# SERIAL_FMU_REV_1B.net
KiCad netlist of a schematic drawn in Altium Designer
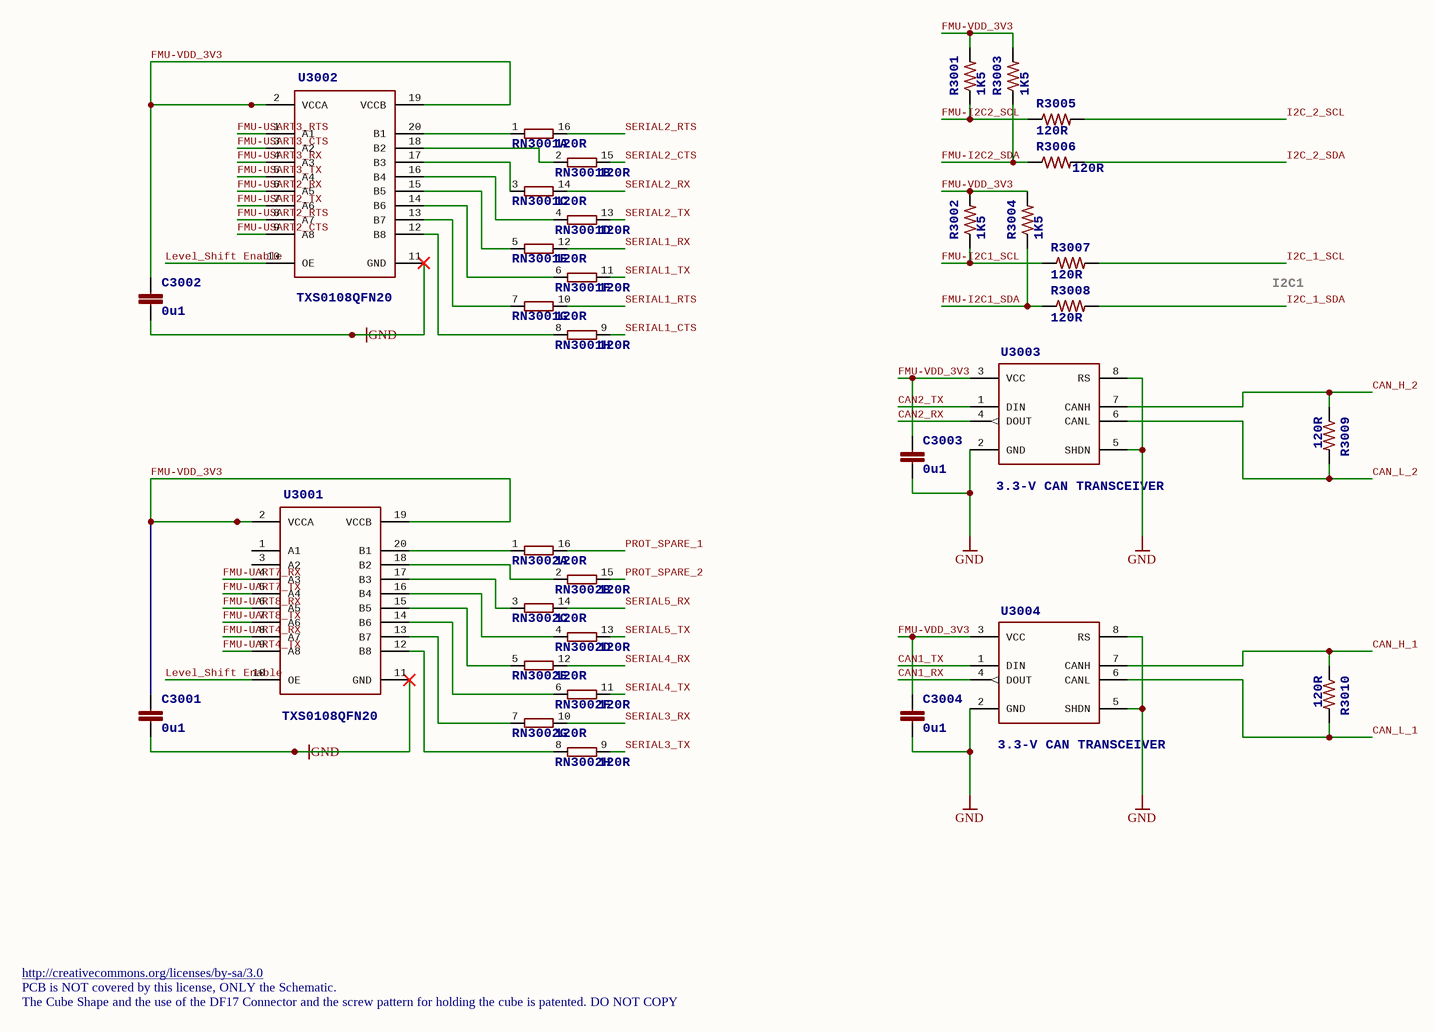
[diagram p0: SERIAL_FMU_REV_1B.SchDoc]

(export (version "E")
  (design (tool "Eeschema 10.0.6"))
  (components
    (comp (ref "C3001")
      (value "0u1")
      (footprint "0402-CAP")
      (description "CAP CER 0.1UF 16V Y5V 0402")
      (libsource (lib "pixhawk2") (part "CAP0402"))
    )
    (comp (ref "C3002")
      (value "0u1")
      (footprint "0402-CAP")
      (description "CAP CER 0.1UF 16V Y5V 0402")
      (libsource (lib "pixhawk2") (part "CAP0402"))
    )
    (comp (ref "C3003")
      (value "0u1")
      (footprint "0402-CAP")
      (description "CAP CER 0.1UF 16V Y5V 0402")
      (libsource (lib "pixhawk2") (part "CAP0402"))
    )
    (comp (ref "C3004")
      (value "0u1")
      (footprint "0402-CAP")
      (description "CAP CER 0.1UF 16V Y5V 0402")
      (libsource (lib "pixhawk2") (part "CAP0402"))
    )
    (comp (ref "R3001")
      (value "1K5")
      (footprint "0402-RES")
      (description "RES 1.5K OHM 1/16W 1% 0402 SMD")
      (libsource (lib "pixhawk2") (part "RESISTOR0402-RES"))
    )
    (comp (ref "R3002")
      (value "1K5")
      (footprint "0402-RES")
      (description "RES 1.5K OHM 1/16W 1% 0402 SMD")
      (libsource (lib "pixhawk2") (part "RESISTOR0402-RES"))
    )
    (comp (ref "R3003")
      (value "1K5")
      (footprint "0402-RES")
      (description "RES 1.5K OHM 1/16W 1% 0402 SMD")
      (libsource (lib "pixhawk2") (part "RESISTOR0402-RES"))
    )
    (comp (ref "R3004")
      (value "1K5")
      (footprint "0402-RES")
      (description "RES 1.5K OHM 1/16W 1% 0402 SMD")
      (libsource (lib "pixhawk2") (part "RESISTOR0402-RES"))
    )
    (comp (ref "R3005")
      (value "120R")
      (footprint "0402-RES")
      (description "RES 120 OHM 1/16W 1% 0402 SMD")
      (libsource (lib "pixhawk2") (part "RESISTOR0402-RES"))
    )
    (comp (ref "R3006")
      (value "120R")
      (footprint "0402-RES")
      (description "RES 120 OHM 1/16W 1% 0402 SMD")
      (libsource (lib "pixhawk2") (part "RESISTOR0402-RES"))
    )
    (comp (ref "R3007")
      (value "120R")
      (footprint "0402-RES")
      (description "RES 120 OHM 1/16W 1% 0402 SMD")
      (libsource (lib "pixhawk2") (part "RESISTOR0402-RES"))
    )
    (comp (ref "R3008")
      (value "120R")
      (footprint "0402-RES")
      (description "RES 120 OHM 1/16W 1% 0402 SMD")
      (libsource (lib "pixhawk2") (part "RESISTOR0402-RES"))
    )
    (comp (ref "R3009")
      (value "120R")
      (footprint "0402-RES")
      (description "RES 120 OHM 1/16W 1% 0402 SMD")
      (libsource (lib "pixhawk2") (part "RESISTOR0402-RES"))
    )
    (comp (ref "R3010")
      (value "120R")
      (footprint "0402-RES")
      (description "RES 120 OHM 1/16W 1% 0402 SMD")
      (libsource (lib "pixhawk2") (part "RESISTOR0402-RES"))
    )
    (comp (ref "RN3001")
      (value "120R")
      (footprint "EXB2HV")
      (description "RES ARRAY 120 OHM 8 RES 1506")
      (libsource (lib "pixhawk2") (part "8R-NEXB2HV-120R"))
    )
    (comp (ref "RN3002")
      (value "120R")
      (footprint "EXB2HV")
      (description "RES ARRAY 120 OHM 8 RES 1506")
      (libsource (lib "pixhawk2") (part "8R-NEXB2HV-120R"))
    )
    (comp (ref "U3001")
      (value "TXS0108QFN20")
      (footprint "QFN20-RGY")
      (description "IC XLATR VOLT-LVL 8B BDIR 20QFN")
      (libsource (lib "pixhawk2") (part "TXS0108QFN20"))
    )
    (comp (ref "U3002")
      (value "TXS0108QFN20")
      (footprint "QFN20-RGY")
      (description "IC XLATR VOLT-LVL 8B BDIR 20QFN")
      (libsource (lib "pixhawk2") (part "TXS0108QFN20"))
    )
    (comp (ref "U3003")
      (value "3.3-V CAN TRANSCEIVER")
      (footprint "SOT23-8")
      (description "IC TXRX CAN 1MBPS SOT23-8")
      (libsource (lib "pixhawk2") (part "MAX3051MAX3051EKA"))
    )
    (comp (ref "U3004")
      (value "3.3-V CAN TRANSCEIVER")
      (footprint "SOT23-8")
      (description "IC TXRX CAN 1MBPS SOT23-8")
      (libsource (lib "pixhawk2") (part "MAX3051MAX3051EKA"))
    )
  )
  (nets
    (net (code "1") (name "/CAN1_RX") (class "Default")
      (node (ref "U3004") (pin "4") (pinfunction "DOUT_4") (pintype "output"))
    )
    (net (code "2") (name "/CAN1_TX") (class "Default")
      (node (ref "U3004") (pin "1") (pinfunction "DIN_1") (pintype "passive"))
    )
    (net (code "3") (name "/CAN2_RX") (class "Default")
      (node (ref "U3003") (pin "4") (pinfunction "DOUT_4") (pintype "output"))
    )
    (net (code "4") (name "/CAN2_TX") (class "Default")
      (node (ref "U3003") (pin "1") (pinfunction "DIN_1") (pintype "passive"))
    )
    (net (code "5") (name "/CAN_H_1") (class "Default")
      (node (ref "R3010") (pin "P$1") (pinfunction "1_P$1") (pintype "passive"))
      (node (ref "U3004") (pin "7") (pinfunction "CANH_7") (pintype "passive"))
    )
    (net (code "6") (name "/CAN_H_2") (class "Default")
      (node (ref "R3009") (pin "P$1") (pinfunction "1_P$1") (pintype "passive"))
      (node (ref "U3003") (pin "7") (pinfunction "CANH_7") (pintype "passive"))
    )
    (net (code "7") (name "/CAN_L_1") (class "Default")
      (node (ref "R3010") (pin "P$2") (pinfunction "2_P$2") (pintype "passive"))
      (node (ref "U3004") (pin "6") (pinfunction "CANL_6") (pintype "passive"))
    )
    (net (code "8") (name "/CAN_L_2") (class "Default")
      (node (ref "R3009") (pin "P$2") (pinfunction "2_P$2") (pintype "passive"))
      (node (ref "U3003") (pin "6") (pinfunction "CANL_6") (pintype "passive"))
    )
    (net (code "9") (name "/FMU-I2C1_SCL") (class "Default")
      (node (ref "R3002") (pin "P$1") (pinfunction "1_P$1") (pintype "passive"))
      (node (ref "R3007") (pin "P$1") (pinfunction "1_P$1") (pintype "passive"))
    )
    (net (code "10") (name "/FMU-I2C1_SDA") (class "Default")
      (node (ref "R3004") (pin "P$1") (pinfunction "1_P$1") (pintype "passive"))
      (node (ref "R3008") (pin "P$1") (pinfunction "1_P$1") (pintype "passive"))
    )
    (net (code "11") (name "/FMU-I2C2_SCL") (class "Default")
      (node (ref "R3001") (pin "P$1") (pinfunction "1_P$1") (pintype "passive"))
      (node (ref "R3005") (pin "P$1") (pinfunction "1_P$1") (pintype "passive"))
    )
    (net (code "12") (name "/FMU-I2C2_SDA") (class "Default")
      (node (ref "R3003") (pin "P$1") (pinfunction "1_P$1") (pintype "passive"))
      (node (ref "R3006") (pin "P$1") (pinfunction "1_P$1") (pintype "passive"))
    )
    (net (code "13") (name "/FMU-UART4_RX") (class "Default")
      (node (ref "U3001") (pin "8") (pinfunction "A7_8") (pintype "passive"))
    )
    (net (code "14") (name "/FMU-UART4_TX") (class "Default")
      (node (ref "U3001") (pin "9") (pinfunction "A8_9") (pintype "passive"))
    )
    (net (code "15") (name "/FMU-UART7_RX") (class "Default")
      (node (ref "U3001") (pin "4") (pinfunction "A3_4") (pintype "passive"))
    )
    (net (code "16") (name "/FMU-UART7_TX") (class "Default")
      (node (ref "U3001") (pin "5") (pinfunction "A4_5") (pintype "passive"))
    )
    (net (code "17") (name "/FMU-UART8_RX") (class "Default")
      (node (ref "U3001") (pin "6") (pinfunction "A5_6") (pintype "passive"))
    )
    (net (code "18") (name "/FMU-UART8_TX") (class "Default")
      (node (ref "U3001") (pin "7") (pinfunction "A6_7") (pintype "passive"))
    )
    (net (code "19") (name "/FMU-USART2_CTS") (class "Default")
      (node (ref "U3002") (pin "9") (pinfunction "A8_9") (pintype "passive"))
    )
    (net (code "20") (name "/FMU-USART2_RTS") (class "Default")
      (node (ref "U3002") (pin "8") (pinfunction "A7_8") (pintype "passive"))
    )
    (net (code "21") (name "/FMU-USART2_RX") (class "Default")
      (node (ref "U3002") (pin "6") (pinfunction "A5_6") (pintype "passive"))
    )
    (net (code "22") (name "/FMU-USART2_TX") (class "Default")
      (node (ref "U3002") (pin "7") (pinfunction "A6_7") (pintype "passive"))
    )
    (net (code "23") (name "/FMU-USART3_CTS") (class "Default")
      (node (ref "U3002") (pin "3") (pinfunction "A2_3") (pintype "passive"))
    )
    (net (code "24") (name "/FMU-USART3_RTS") (class "Default")
      (node (ref "U3002") (pin "1") (pinfunction "A1_1") (pintype "passive"))
    )
    (net (code "25") (name "/FMU-USART3_RX") (class "Default")
      (node (ref "U3002") (pin "4") (pinfunction "A3_4") (pintype "passive"))
    )
    (net (code "26") (name "/FMU-USART3_TX") (class "Default")
      (node (ref "U3002") (pin "5") (pinfunction "A4_5") (pintype "passive"))
    )
    (net (code "27") (name "/FMU-VDD_3V3") (class "Default")
      (node (ref "C3001") (pin "P$1") (pinfunction "1_P$1") (pintype "passive"))
      (node (ref "C3002") (pin "P$1") (pinfunction "1_P$1") (pintype "passive"))
      (node (ref "C3003") (pin "P$1") (pinfunction "1_P$1") (pintype "passive"))
      (node (ref "C3004") (pin "P$1") (pinfunction "1_P$1") (pintype "passive"))
      (node (ref "R3001") (pin "P$2") (pinfunction "2_P$2") (pintype "passive"))
      (node (ref "R3002") (pin "P$2") (pinfunction "2_P$2") (pintype "passive"))
      (node (ref "R3003") (pin "P$2") (pinfunction "2_P$2") (pintype "passive"))
      (node (ref "R3004") (pin "P$2") (pinfunction "2_P$2") (pintype "passive"))
      (node (ref "U3001") (pin "19") (pinfunction "VCCB_19") (pintype "passive"))
      (node (ref "U3001") (pin "2") (pinfunction "VCCA_2") (pintype "passive"))
      (node (ref "U3002") (pin "19") (pinfunction "VCCB_19") (pintype "passive"))
      (node (ref "U3002") (pin "2") (pinfunction "VCCA_2") (pintype "passive"))
      (node (ref "U3003") (pin "3") (pinfunction "VCC_3") (pintype "passive"))
      (node (ref "U3004") (pin "3") (pinfunction "VCC_3") (pintype "passive"))
    )
    (net (code "28") (name "/I2C_1_SCL") (class "Default")
      (node (ref "R3007") (pin "P$2") (pinfunction "2_P$2") (pintype "passive"))
    )
    (net (code "29") (name "/I2C_1_SDA") (class "Default")
      (node (ref "R3008") (pin "P$2") (pinfunction "2_P$2") (pintype "passive"))
    )
    (net (code "30") (name "/I2C_2_SCL") (class "Default")
      (node (ref "R3005") (pin "P$2") (pinfunction "2_P$2") (pintype "passive"))
    )
    (net (code "31") (name "/I2C_2_SDA") (class "Default")
      (node (ref "R3006") (pin "P$2") (pinfunction "2_P$2") (pintype "passive"))
    )
    (net (code "32") (name "/Level_Shift Enable") (class "Default")
      (node (ref "U3001") (pin "10") (pinfunction "OE_10") (pintype "passive"))
      (node (ref "U3002") (pin "10") (pinfunction "OE_10") (pintype "passive"))
    )
    (net (code "33") (name "/PROT_SPARE_1") (class "Default")
      (node (ref "RN3002") (pin "16") (pinfunction "2_16") (pintype "passive"))
    )
    (net (code "34") (name "/PROT_SPARE_2") (class "Default")
      (node (ref "RN3002") (pin "15") (pinfunction "2_15") (pintype "passive"))
    )
    (net (code "35") (name "/SERIAL1_CTS") (class "Default")
      (node (ref "RN3001") (pin "9") (pinfunction "2_9") (pintype "passive"))
    )
    (net (code "36") (name "/SERIAL1_RTS") (class "Default")
      (node (ref "RN3001") (pin "10") (pinfunction "2_10") (pintype "passive"))
    )
    (net (code "37") (name "/SERIAL1_RX") (class "Default")
      (node (ref "RN3001") (pin "12") (pinfunction "2_12") (pintype "passive"))
    )
    (net (code "38") (name "/SERIAL1_TX") (class "Default")
      (node (ref "RN3001") (pin "11") (pinfunction "2_11") (pintype "passive"))
    )
    (net (code "39") (name "/SERIAL2_CTS") (class "Default")
      (node (ref "RN3001") (pin "15") (pinfunction "2_15") (pintype "passive"))
    )
    (net (code "40") (name "/SERIAL2_RTS") (class "Default")
      (node (ref "RN3001") (pin "16") (pinfunction "2_16") (pintype "passive"))
    )
    (net (code "41") (name "/SERIAL2_RX") (class "Default")
      (node (ref "RN3001") (pin "14") (pinfunction "2_14") (pintype "passive"))
    )
    (net (code "42") (name "/SERIAL2_TX") (class "Default")
      (node (ref "RN3001") (pin "13") (pinfunction "2_13") (pintype "passive"))
    )
    (net (code "43") (name "/SERIAL3_RX") (class "Default")
      (node (ref "RN3002") (pin "10") (pinfunction "2_10") (pintype "passive"))
    )
    (net (code "44") (name "/SERIAL3_TX") (class "Default")
      (node (ref "RN3002") (pin "9") (pinfunction "2_9") (pintype "passive"))
    )
    (net (code "45") (name "/SERIAL4_RX") (class "Default")
      (node (ref "RN3002") (pin "12") (pinfunction "2_12") (pintype "passive"))
    )
    (net (code "46") (name "/SERIAL4_TX") (class "Default")
      (node (ref "RN3002") (pin "11") (pinfunction "2_11") (pintype "passive"))
    )
    (net (code "47") (name "/SERIAL5_RX") (class "Default")
      (node (ref "RN3002") (pin "14") (pinfunction "2_14") (pintype "passive"))
    )
    (net (code "48") (name "/SERIAL5_TX") (class "Default")
      (node (ref "RN3002") (pin "13") (pinfunction "2_13") (pintype "passive"))
    )
    (net (code "49") (name "GND") (class "Default")
      (node (ref "C3001") (pin "P$2") (pinfunction "2_P$2") (pintype "passive"))
      (node (ref "C3002") (pin "P$2") (pinfunction "2_P$2") (pintype "passive"))
      (node (ref "C3003") (pin "P$2") (pinfunction "2_P$2") (pintype "passive"))
      (node (ref "C3004") (pin "P$2") (pinfunction "2_P$2") (pintype "passive"))
      (node (ref "U3001") (pin "11") (pinfunction "GND_11") (pintype "open_emitter"))
      (node (ref "U3002") (pin "11") (pinfunction "GND_11") (pintype "open_emitter"))
      (node (ref "U3003") (pin "2") (pinfunction "GND_2") (pintype "open_emitter"))
      (node (ref "U3003") (pin "5") (pinfunction "SHDN_5") (pintype "passive"))
      (node (ref "U3003") (pin "8") (pinfunction "RS_8") (pintype "passive"))
      (node (ref "U3004") (pin "2") (pinfunction "GND_2") (pintype "open_emitter"))
      (node (ref "U3004") (pin "5") (pinfunction "SHDN_5") (pintype "passive"))
      (node (ref "U3004") (pin "8") (pinfunction "RS_8") (pintype "passive"))
    )
    (net (code "50") (name "Net-(RN3001B-1)") (class "Default")
      (node (ref "RN3001") (pin "2") (pinfunction "1_2") (pintype "passive"))
      (node (ref "U3002") (pin "18") (pinfunction "B2_18") (pintype "passive"))
    )
    (net (code "51") (name "Net-(RN3001C-1)") (class "Default")
      (node (ref "RN3001") (pin "3") (pinfunction "1_3") (pintype "passive"))
      (node (ref "U3002") (pin "17") (pinfunction "B3_17") (pintype "passive"))
    )
    (net (code "52") (name "Net-(RN3001D-1)") (class "Default")
      (node (ref "RN3001") (pin "4") (pinfunction "1_4") (pintype "passive"))
      (node (ref "U3002") (pin "16") (pinfunction "B4_16") (pintype "passive"))
    )
    (net (code "53") (name "Net-(RN3001E-1)") (class "Default")
      (node (ref "RN3001") (pin "5") (pinfunction "1_5") (pintype "passive"))
      (node (ref "U3002") (pin "15") (pinfunction "B5_15") (pintype "passive"))
    )
    (net (code "54") (name "Net-(RN3001F-1)") (class "Default")
      (node (ref "RN3001") (pin "6") (pinfunction "1_6") (pintype "passive"))
      (node (ref "U3002") (pin "14") (pinfunction "B6_14") (pintype "passive"))
    )
    (net (code "55") (name "Net-(RN3001G-1)") (class "Default")
      (node (ref "RN3001") (pin "7") (pinfunction "1_7") (pintype "passive"))
      (node (ref "U3002") (pin "13") (pinfunction "B7_13") (pintype "passive"))
    )
    (net (code "56") (name "Net-(RN3001H-1)") (class "Default")
      (node (ref "RN3001") (pin "8") (pinfunction "1_8") (pintype "passive"))
      (node (ref "U3002") (pin "12") (pinfunction "B8_12") (pintype "passive"))
    )
    (net (code "57") (name "Net-(RN3002B-1)") (class "Default")
      (node (ref "RN3002") (pin "2") (pinfunction "1_2") (pintype "passive"))
      (node (ref "U3001") (pin "18") (pinfunction "B2_18") (pintype "passive"))
    )
    (net (code "58") (name "Net-(RN3002C-1)") (class "Default")
      (node (ref "RN3002") (pin "3") (pinfunction "1_3") (pintype "passive"))
      (node (ref "U3001") (pin "17") (pinfunction "B3_17") (pintype "passive"))
    )
    (net (code "59") (name "Net-(RN3002D-1)") (class "Default")
      (node (ref "RN3002") (pin "4") (pinfunction "1_4") (pintype "passive"))
      (node (ref "U3001") (pin "16") (pinfunction "B4_16") (pintype "passive"))
    )
    (net (code "60") (name "Net-(RN3002E-1)") (class "Default")
      (node (ref "RN3002") (pin "5") (pinfunction "1_5") (pintype "passive"))
      (node (ref "U3001") (pin "15") (pinfunction "B5_15") (pintype "passive"))
    )
    (net (code "61") (name "Net-(RN3002F-1)") (class "Default")
      (node (ref "RN3002") (pin "6") (pinfunction "1_6") (pintype "passive"))
      (node (ref "U3001") (pin "14") (pinfunction "B6_14") (pintype "passive"))
    )
    (net (code "62") (name "Net-(RN3002G-1)") (class "Default")
      (node (ref "RN3002") (pin "7") (pinfunction "1_7") (pintype "passive"))
      (node (ref "U3001") (pin "13") (pinfunction "B7_13") (pintype "passive"))
    )
    (net (code "63") (name "Net-(RN3002H-1)") (class "Default")
      (node (ref "RN3002") (pin "8") (pinfunction "1_8") (pintype "passive"))
      (node (ref "U3001") (pin "12") (pinfunction "B8_12") (pintype "passive"))
    )
    (net (code "64") (name "Net-(U3001-B1)") (class "Default")
      (node (ref "RN3002") (pin "1") (pinfunction "1_1") (pintype "passive"))
      (node (ref "U3001") (pin "20") (pinfunction "B1_20") (pintype "passive"))
    )
    (net (code "65") (name "Net-(U3002-B1)") (class "Default")
      (node (ref "RN3001") (pin "1") (pinfunction "1_1") (pintype "passive"))
      (node (ref "U3002") (pin "20") (pinfunction "B1_20") (pintype "passive"))
    )
    (net (code "66") (name "unconnected-(U3001-A1-Pad1)") (class "Default")
      (node (ref "U3001") (pin "1") (pinfunction "A1_1") (pintype "passive"))
    )
    (net (code "67") (name "unconnected-(U3001-A2-Pad3)") (class "Default")
      (node (ref "U3001") (pin "3") (pinfunction "A2_3") (pintype "passive"))
    )
  )
)
